# yep.net
KiCad netlist of a schematic drawn in EAGLE
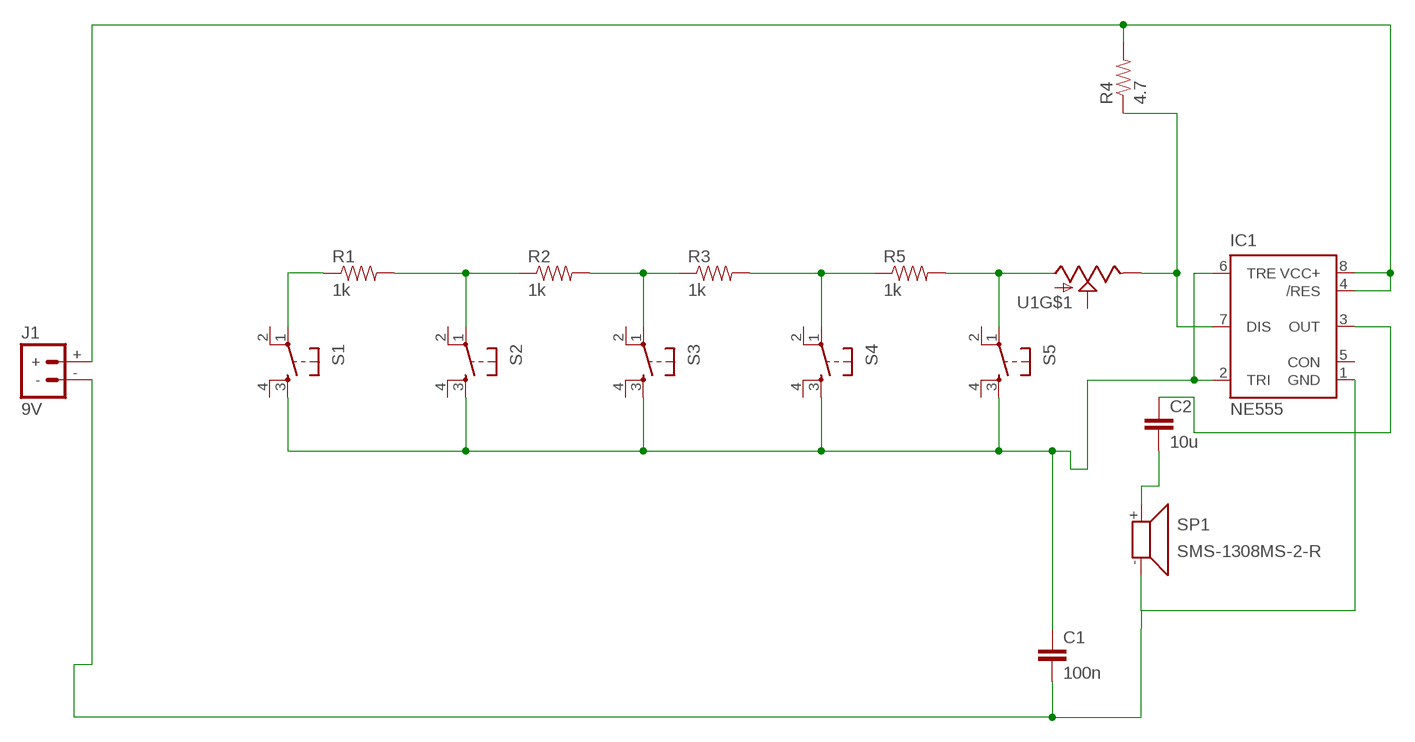
[diagram p0: schematic, sheet 1]

(export (version "E")
  (design (tool "Eeschema 10.0.6"))
  (components
    (comp (ref "C1")
      (value "100n")
      (footprint "eagle-import:0603-CAP")
      (libsource (lib "eagle-import") (part "CAP0603-CAP"))
    )
    (comp (ref "C2")
      (value "10u")
      (footprint "eagle-import:0603-CAP")
      (libsource (lib "eagle-import") (part "CAP0603-CAP"))
    )
    (comp (ref "IC1")
      (value "NE555")
      (footprint "eagle-import:DIL-08")
      (fields (field (name "MF") "Arrow Electronics") (field (name "MPN") "NE555N"))
      (libsource (lib "eagle-import") (part "NE555"))
    )
    (comp (ref "J1")
      (value "9V")
      (footprint "eagle-import:DEANS")
      (libsource (lib "eagle-import") (part "BATTERY_CONNDEANS"))
    )
    (comp (ref "R1")
      (value "1k")
      (footprint "eagle-import:0603-RES")
      (libsource (lib "eagle-import") (part "RESISTOR0603-RES"))
    )
    (comp (ref "R2")
      (value "1k")
      (footprint "eagle-import:0603-RES")
      (libsource (lib "eagle-import") (part "RESISTOR0603-RES"))
    )
    (comp (ref "R3")
      (value "1k")
      (footprint "eagle-import:0603-RES")
      (libsource (lib "eagle-import") (part "RESISTOR0603-RES"))
    )
    (comp (ref "R4")
      (value "4.7")
      (footprint "eagle-import:0603-RES")
      (libsource (lib "eagle-import") (part "RESISTOR0603-RES"))
    )
    (comp (ref "R5")
      (value "1k")
      (footprint "eagle-import:0603-RES")
      (libsource (lib "eagle-import") (part "RESISTOR0603-RES"))
    )
    (comp (ref "S1")
      (value "TAC_SWITCHPTH")
      (footprint "eagle-import:TACTILE-PTH")
      (libsource (lib "eagle-import") (part "TAC_SWITCHPTH"))
    )
    (comp (ref "S2")
      (value "TAC_SWITCHPTH")
      (footprint "eagle-import:TACTILE-PTH")
      (libsource (lib "eagle-import") (part "TAC_SWITCHPTH"))
    )
    (comp (ref "S3")
      (value "TAC_SWITCHPTH")
      (footprint "eagle-import:TACTILE-PTH")
      (libsource (lib "eagle-import") (part "TAC_SWITCHPTH"))
    )
    (comp (ref "S4")
      (value "TAC_SWITCHPTH")
      (footprint "eagle-import:TACTILE-PTH")
      (libsource (lib "eagle-import") (part "TAC_SWITCHPTH"))
    )
    (comp (ref "S5")
      (value "TAC_SWITCHPTH")
      (footprint "eagle-import:TACTILE-PTH")
      (libsource (lib "eagle-import") (part "TAC_SWITCHPTH"))
    )
    (comp (ref "SP1")
      (value "SMS-1308MS-2-R")
      (footprint "eagle-import:SMS-1308MS-2-R")
      (libsource (lib "eagle-import") (part "SMS-1308MS-2-R"))
    )
    (comp (ref "U1")
      (value "POT_SWITCHPOT_PTH")
      (footprint "eagle-import:POT_PTH")
      (libsource (lib "eagle-import") (part "POT_SWITCHPOT_PTH"))
    )
  )
  (nets
    (net (code "1") (name "Net-(IC1-DIS)") (class "Default")
      (node (ref "IC1") (pin "7") (pinfunction "DIS_7") (pintype "input"))
      (node (ref "R4") (pin "1") (pinfunction "1_1") (pintype "passive"))
      (node (ref "U1") (pin "E@2") (pinfunction "E_E@2") (pintype "passive"))
    )
    (net (code "2") (name "Net-(IC1-GND)") (class "Default")
      (node (ref "C1") (pin "2") (pinfunction "2_2") (pintype "passive"))
      (node (ref "IC1") (pin "1") (pinfunction "GND_1") (pintype "power_in"))
      (node (ref "J1") (pin "-") (pinfunction "-_-") (pintype "passive"))
      (node (ref "SP1") (pin "-") (pinfunction "2_-") (pintype "passive"))
    )
    (net (code "3") (name "Net-(IC1-OUT)") (class "Default")
      (node (ref "C2") (pin "1") (pinfunction "1_1") (pintype "passive"))
      (node (ref "IC1") (pin "3") (pinfunction "OUT_3") (pintype "output"))
    )
    (net (code "4") (name "Net-(IC1-TRE)") (class "Default")
      (node (ref "C1") (pin "1") (pinfunction "1_1") (pintype "passive"))
      (node (ref "IC1") (pin "2") (pinfunction "TRI_2") (pintype "input"))
      (node (ref "IC1") (pin "6") (pinfunction "TRE_6") (pintype "input"))
      (node (ref "S1") (pin "3") (pinfunction "3_3") (pintype "passive"))
      (node (ref "S2") (pin "3") (pinfunction "3_3") (pintype "passive"))
      (node (ref "S3") (pin "3") (pinfunction "3_3") (pintype "passive"))
      (node (ref "S4") (pin "3") (pinfunction "3_3") (pintype "passive"))
      (node (ref "S5") (pin "3") (pinfunction "3_3") (pintype "passive"))
    )
    (net (code "5") (name "Net-(IC1-VCC+)") (class "Default")
      (node (ref "IC1") (pin "4") (pinfunction "/RES_4") (pintype "input"))
      (node (ref "IC1") (pin "8") (pinfunction "VCC+_8") (pintype "power_in"))
      (node (ref "J1") (pin "+") (pinfunction "+_+") (pintype "passive"))
      (node (ref "R4") (pin "2") (pinfunction "2_2") (pintype "passive"))
    )
    (net (code "6") (name "Net-(R1-Pad1)") (class "Default")
      (node (ref "R1") (pin "1") (pinfunction "1_1") (pintype "passive"))
      (node (ref "S1") (pin "1") (pinfunction "1_1") (pintype "passive"))
    )
    (net (code "7") (name "Net-(R1-Pad2)") (class "Default")
      (node (ref "R1") (pin "2") (pinfunction "2_2") (pintype "passive"))
      (node (ref "R2") (pin "1") (pinfunction "1_1") (pintype "passive"))
      (node (ref "S2") (pin "1") (pinfunction "1_1") (pintype "passive"))
    )
    (net (code "8") (name "Net-(R2-Pad2)") (class "Default")
      (node (ref "R2") (pin "2") (pinfunction "2_2") (pintype "passive"))
      (node (ref "R3") (pin "1") (pinfunction "1_1") (pintype "passive"))
      (node (ref "S3") (pin "1") (pinfunction "1_1") (pintype "passive"))
    )
    (net (code "9") (name "Net-(R3-Pad2)") (class "Default")
      (node (ref "R3") (pin "2") (pinfunction "2_2") (pintype "passive"))
      (node (ref "R5") (pin "1") (pinfunction "1_1") (pintype "passive"))
      (node (ref "S4") (pin "1") (pinfunction "1_1") (pintype "passive"))
    )
    (net (code "10") (name "Net-(R5-Pad2)") (class "Default")
      (node (ref "R5") (pin "2") (pinfunction "2_2") (pintype "passive"))
      (node (ref "S5") (pin "1") (pinfunction "1_1") (pintype "passive"))
    )
    (net (code "11") (name "Net-(SP1-1)") (class "Default")
      (node (ref "C2") (pin "2") (pinfunction "2_2") (pintype "passive"))
      (node (ref "SP1") (pin "+") (pinfunction "1_+") (pintype "passive"))
    )
    (net (code "12") (name "unconnected-(IC1-CON-Pad5)") (class "Default")
      (node (ref "IC1") (pin "5") (pinfunction "CON_5") (pintype "input"))
    )
    (net (code "13") (name "unconnected-(S1-Pad2)") (class "Default")
      (node (ref "S1") (pin "2") (pinfunction "2_2") (pintype "passive"))
    )
    (net (code "14") (name "unconnected-(S1-Pad4)") (class "Default")
      (node (ref "S1") (pin "4") (pinfunction "4_4") (pintype "passive"))
    )
    (net (code "15") (name "unconnected-(S2-Pad2)") (class "Default")
      (node (ref "S2") (pin "2") (pinfunction "2_2") (pintype "passive"))
    )
    (net (code "16") (name "unconnected-(S2-Pad4)") (class "Default")
      (node (ref "S2") (pin "4") (pinfunction "4_4") (pintype "passive"))
    )
    (net (code "17") (name "unconnected-(S3-Pad2)") (class "Default")
      (node (ref "S3") (pin "2") (pinfunction "2_2") (pintype "passive"))
    )
    (net (code "18") (name "unconnected-(S3-Pad4)") (class "Default")
      (node (ref "S3") (pin "4") (pinfunction "4_4") (pintype "passive"))
    )
    (net (code "19") (name "unconnected-(S4-Pad2)") (class "Default")
      (node (ref "S4") (pin "2") (pinfunction "2_2") (pintype "passive"))
    )
    (net (code "20") (name "unconnected-(S4-Pad4)") (class "Default")
      (node (ref "S4") (pin "4") (pinfunction "4_4") (pintype "passive"))
    )
    (net (code "21") (name "unconnected-(S5-Pad2)") (class "Default")
      (node (ref "S5") (pin "2") (pinfunction "2_2") (pintype "passive"))
    )
    (net (code "22") (name "unconnected-(S5-Pad4)") (class "Default")
      (node (ref "S5") (pin "4") (pinfunction "4_4") (pintype "passive"))
    )
    (net (code "23") (name "unconnected-(U1A-A-PadE@1)") (class "Default")
      (node (ref "U1") (pin "E@1") (pinfunction "A_E@1") (pintype "passive"))
    )
    (net (code "24") (name "unconnected-(U1A-S-PadWAND)") (class "Default")
      (node (ref "U1") (pin "WAND") (pinfunction "S_WAND") (pintype "passive"))
    )
  )
)
